# schematic.net
KiCad netlist of a schematic drawn in EasyEDA
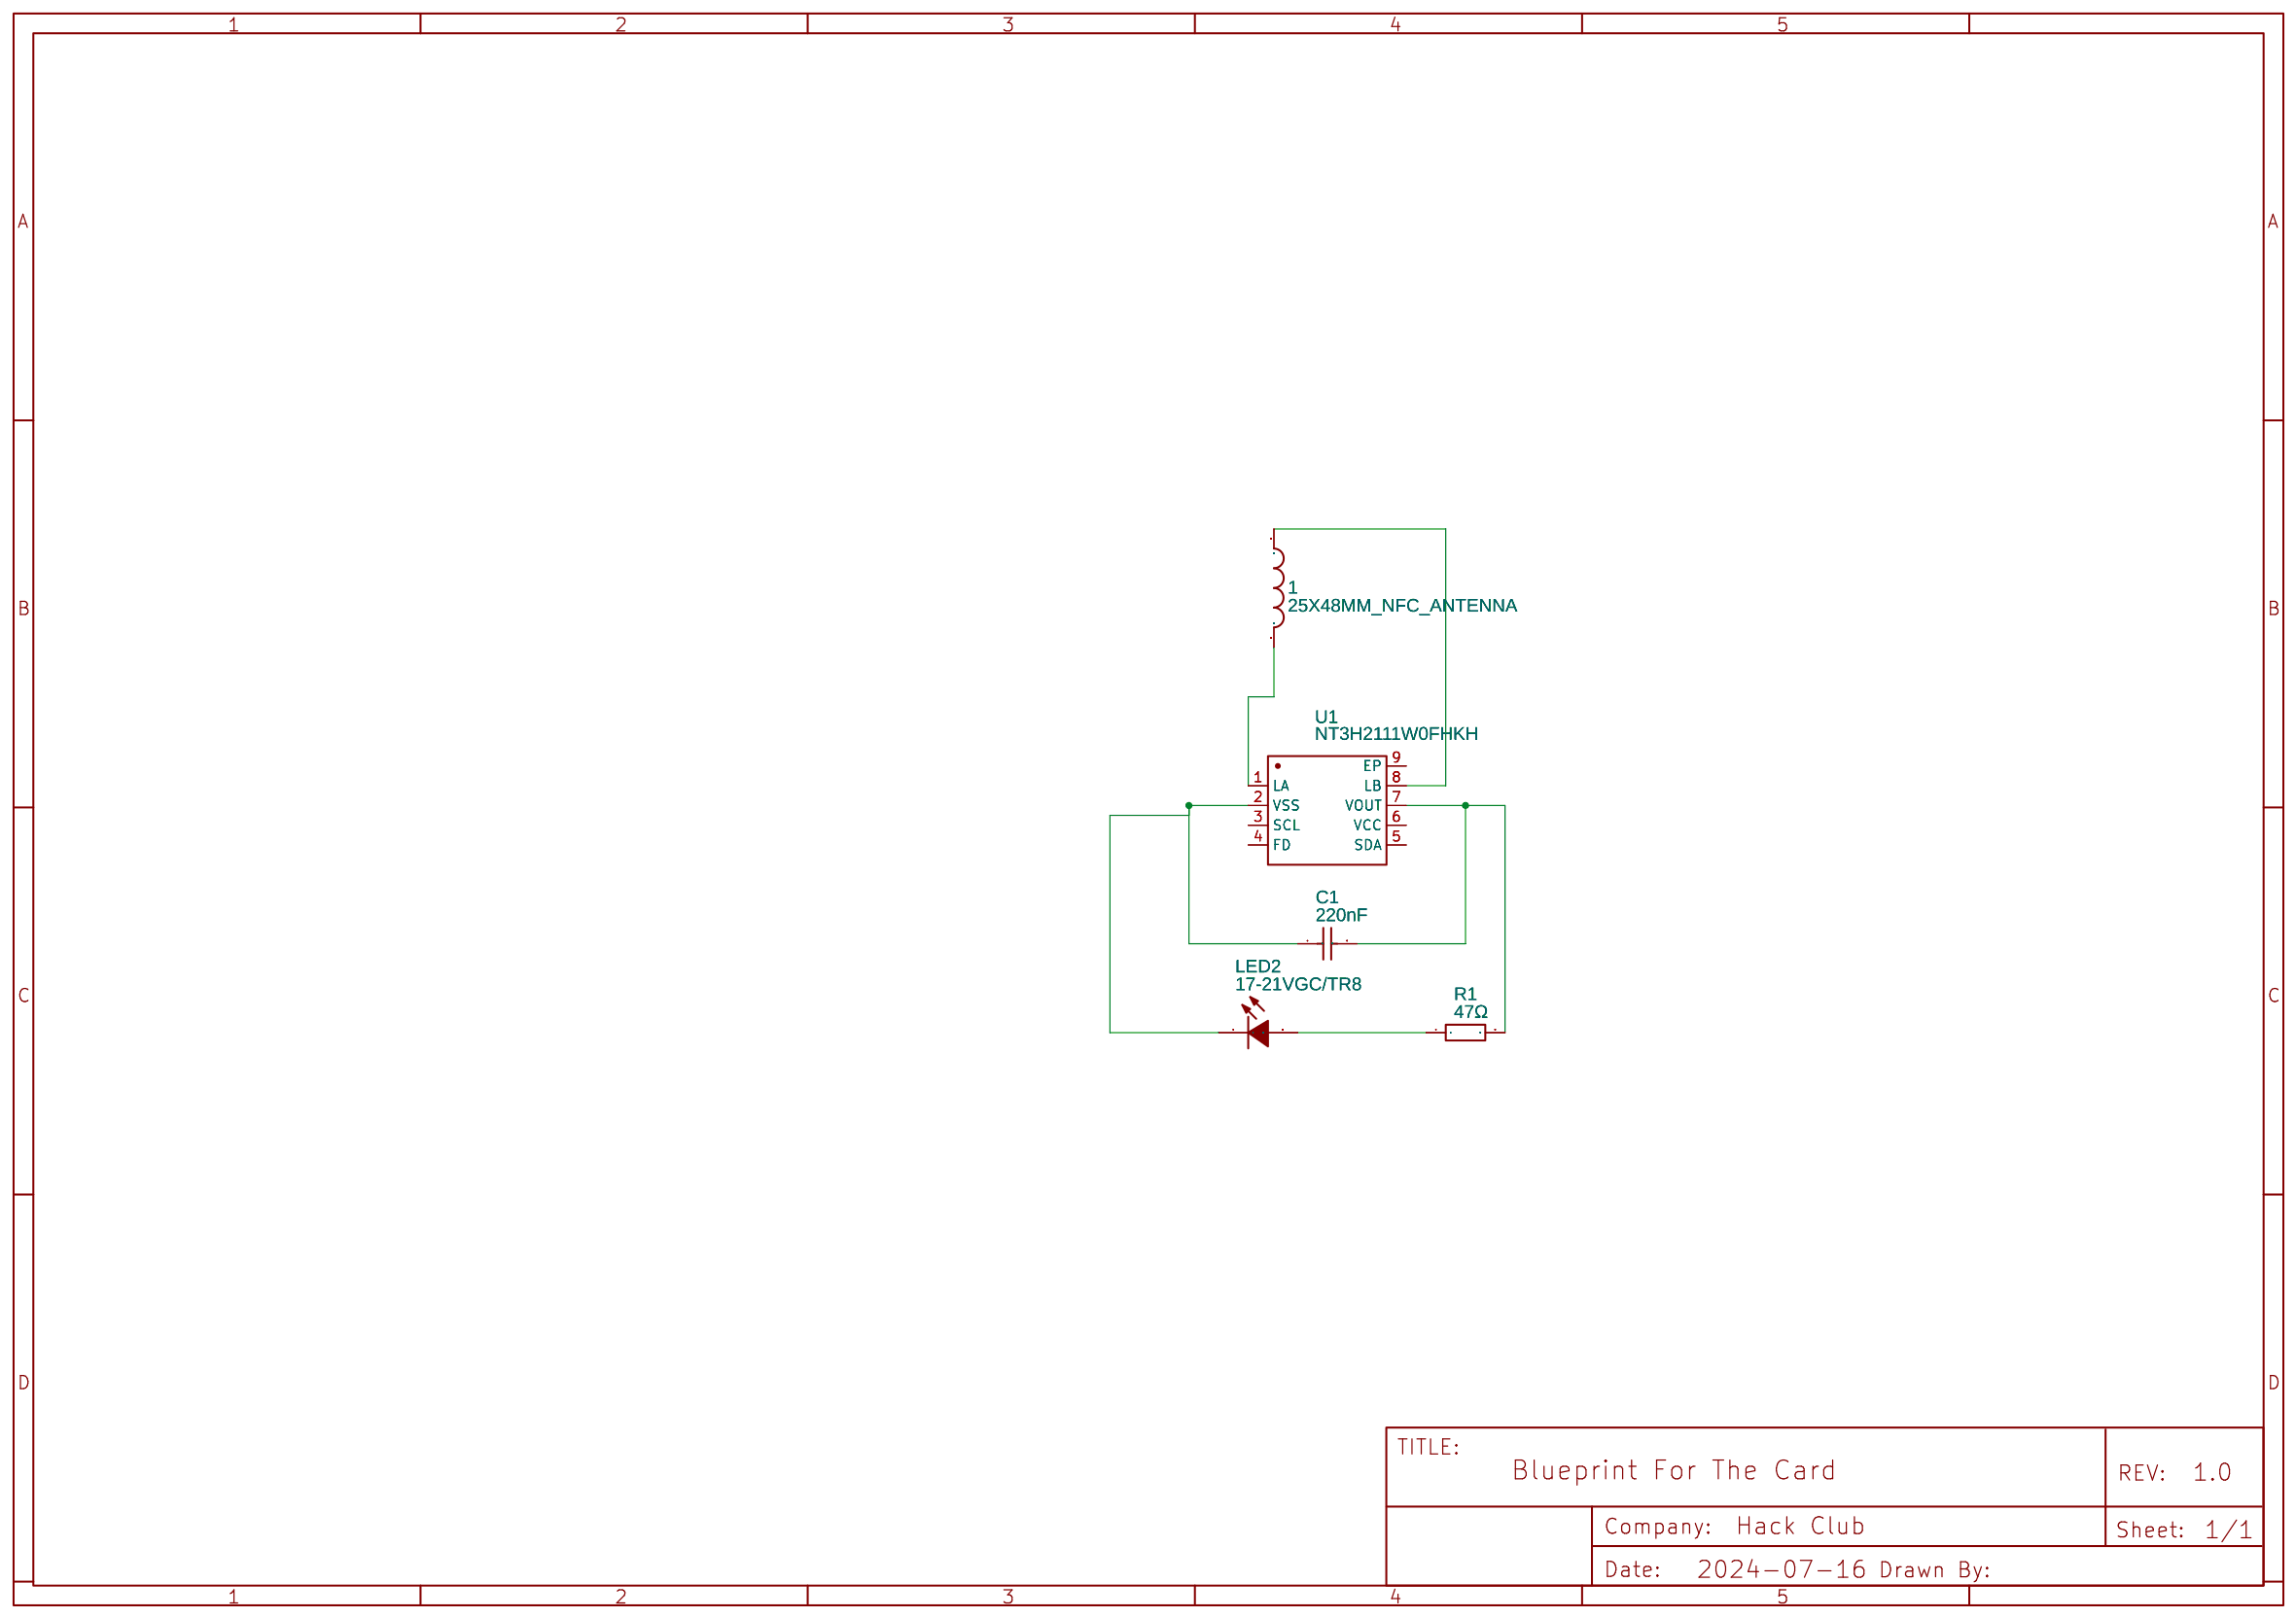
[diagram p0: schematic sheet]

(export (version "E")
  (design (tool "Eeschema 10.0.6"))
  (components
    (comp (ref "1") (value "25X48MM_NFC_ANTENNA") (libsource (lib "") (part "25X48MM_NFC_ANTENNA")))
    (comp (ref "C1")
      (value "220nF")
      (fields
        (field (name "Manufacturer Part") "CL10B224KA8NNNC")
        (field (name "Manufacturer") "SAMSUNG(三星)")
      )
      (libsource (lib "") (part "CL10B224KA8NNNC"))
    )
    (comp (ref "LED2")
      (value "17-21VGC/TR8")
      (fields (field (name "Manufacturer") "EVERLIGHT(亿光)"))
      (libsource (lib "") (part "17-21VGC/TR8"))
    )
    (comp (ref "R1")
      (value "47Ω")
      (fields
        (field (name "Manufacturer Part") "0603WAF470JT5E")
        (field (name "Manufacturer") "UNI-ROYAL(厚声)")
      )
      (libsource (lib "") (part "0603WAF470JT5E"))
    )
    (comp (ref "U1")
      (value "NT3H2111W0FHKH")
      (fields (field (name "Manufacturer") "NXP(恩智浦)"))
      (libsource (lib "") (part "NT3H2111W0FHKH"))
    )
  )
  (nets
    (net (code "1") (name "Net-(LED2-+)") (class "Default")
      (node (ref "LED2") (pin "2") (pinfunction "+_2") (pintype "unspecified"))
      (node (ref "R1") (pin "1") (pinfunction "1_1") (pintype "input"))
    )
    (net (code "2") (name "Net-(LED2--)") (class "Default")
      (node (ref "C1") (pin "1") (pinfunction "1_1") (pintype "input"))
      (node (ref "LED2") (pin "1") (pinfunction "-_1") (pintype "unspecified"))
      (node (ref "U1") (pin "2") (pinfunction "VSS_2") (pintype "unspecified"))
    )
    (net (code "3") (name "Net-(U1-LA)") (class "Default")
      (node (ref "1") (pin "P$2") (pinfunction "P$2_P$2") (pintype "bidirectional"))
      (node (ref "U1") (pin "1") (pinfunction "LA_1") (pintype "unspecified"))
    )
    (net (code "4") (name "Net-(U1-LB)") (class "Default")
      (node (ref "1") (pin "P$1") (pinfunction "P$1_P$1") (pintype "bidirectional"))
      (node (ref "U1") (pin "8") (pinfunction "LB_8") (pintype "unspecified"))
    )
    (net (code "5") (name "Net-(U1-VOUT)") (class "Default")
      (node (ref "C1") (pin "2") (pinfunction "2_2") (pintype "input"))
      (node (ref "R1") (pin "2") (pinfunction "2_2") (pintype "input"))
      (node (ref "U1") (pin "7") (pinfunction "VOUT_7") (pintype "unspecified"))
    )
    (net (code "6") (name "unconnected-(U1-EP-Pad9)") (class "Default")
      (node (ref "U1") (pin "9") (pinfunction "EP_9") (pintype "unspecified"))
    )
    (net (code "7") (name "unconnected-(U1-FD-Pad4)") (class "Default")
      (node (ref "U1") (pin "4") (pinfunction "FD_4") (pintype "unspecified"))
    )
    (net (code "8") (name "unconnected-(U1-SCL-Pad3)") (class "Default")
      (node (ref "U1") (pin "3") (pinfunction "SCL_3") (pintype "unspecified"))
    )
    (net (code "9") (name "unconnected-(U1-SDA-Pad5)") (class "Default")
      (node (ref "U1") (pin "5") (pinfunction "SDA_5") (pintype "unspecified"))
    )
    (net (code "10") (name "unconnected-(U1-VCC-Pad6)") (class "Default")
      (node (ref "U1") (pin "6") (pinfunction "VCC_6") (pintype "unspecified"))
    )
  )
)
